# Relays.net
KiCad netlist of a schematic drawn in Altium Designer
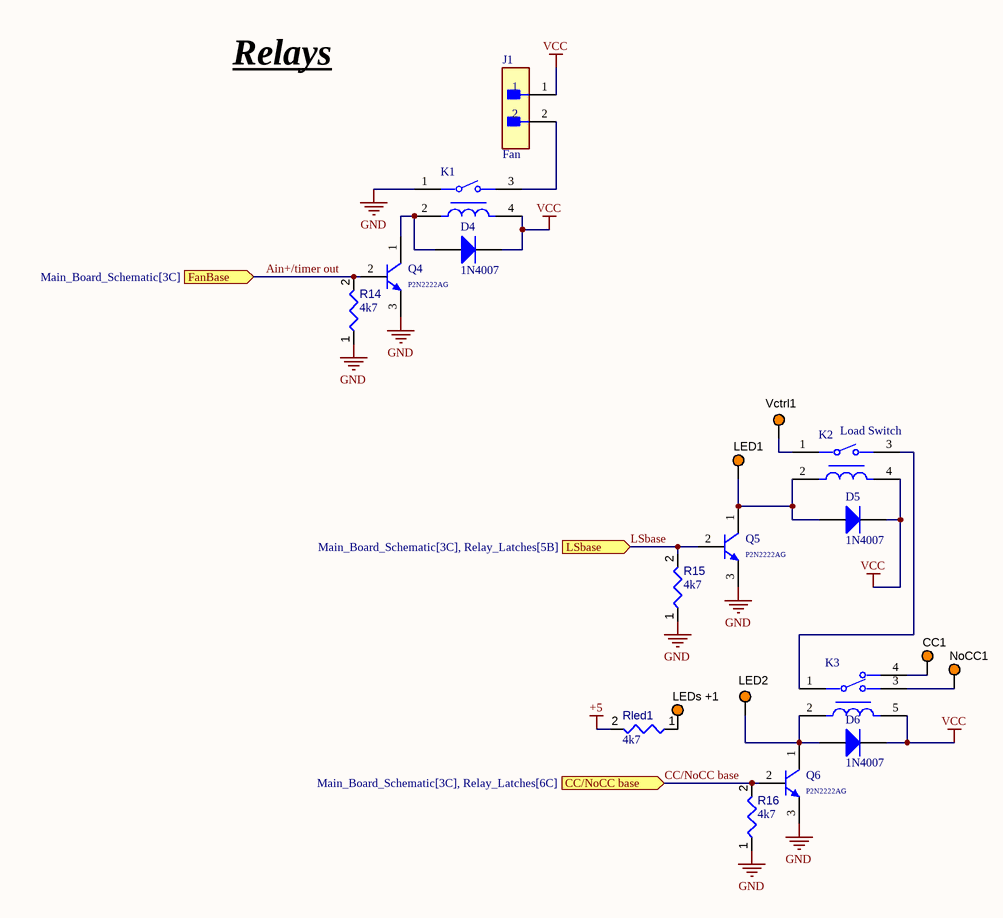
[diagram p0: Relays.SchDoc]

(export (version "E")
  (design (tool "Eeschema 10.0.6"))
  (components
    (comp (ref "CC1")
      (value "5003")
      (footprint "KSTN-5003")
      (description "Test Point, Orange, Height 4.6 mm, Tail Length 3 mm, 1-Pin THD, RoHS")
      (fields (field (name "MANUFACTURER") "Keystone"))
      (libsource (lib "Konstantinos Psarras") (part "TESTPOINT_ORANGE"))
    )
    (comp (ref "D4")
      (value "1N4007")
      (footprint "FAIR-DO-41-2")
      (description "General Purpose Rectifier, 1.1 V, 1.0 A, -55 to 175 degC, 2-Pin DO-41, RoHS, Tape and Reel")
      (fields (field (name "MANUFACTURER") "Fairchild"))
      (libsource (lib "Konstantinos Psarras") (part "KESE-D_K1A2-2"))
    )
    (comp (ref "D5")
      (value "1N4007")
      (footprint "FAIR-DO-41-2")
      (description "General Purpose Rectifier, 1.1 V, 1.0 A, -55 to 175 degC, 2-Pin DO-41, RoHS, Tape and Reel")
      (fields (field (name "MANUFACTURER") "Fairchild"))
      (libsource (lib "Konstantinos Psarras") (part "KESE-D_K1A2-2"))
    )
    (comp (ref "D6")
      (value "1N4007")
      (footprint "FAIR-DO-41-2")
      (description "General Purpose Rectifier, 1.1 V, 1.0 A, -55 to 175 degC, 2-Pin DO-41, RoHS, Tape and Reel")
      (fields (field (name "MANUFACTURER") "Fairchild"))
      (libsource (lib "Konstantinos Psarras") (part "KESE-D_K1A2-2"))
    )
    (comp (ref "J1")
      (value "Fan")
      (footprint "FP-B2B-XH-A_LF_SN-MFG")
      (description "CONN HEADER VERT 2POS 2.5MM")
      (libsource (lib "Altium Content Vault") (part "3bc925449376181038e59eaffc5286c"))
    )
    (comp (ref "K1")
      (value "LKQ1AF-5V-TV-5")
      (footprint "FP-LKQ1AF-5V-TV-5-MFG")
      (description "Quiet Type, High Sensitivity 250MW, Slim Power Relay")
      (libsource (lib "Konstantinos Psarras") (part "efdf740da079d6e8343da2175463948"))
    )
    (comp (ref "K2")
      (value "Load Switch")
      (footprint "FP-LKQ1AF-5V-TV-5-MFG")
      (description "Quiet Type, High Sensitivity 250MW, Slim Power Relay")
      (libsource (lib "Konstantinos Psarras") (part "efdf740da079d6e8343da2175463948"))
    )
    (comp (ref "K3")
      (value "G5LE-14-36 DC12")
      (footprint "FP-G5LE-14-36_DC12-MFG")
      (description "RELAY GEN PURPOSE SPDT 10A 12V")
      (libsource (lib "Altium Content Vault") (part "c03b8d08e5d02e70a6880f365e34168"))
    )
    (comp (ref "LED1")
      (value "5003")
      (footprint "KSTN-5003")
      (description "Test Point, Orange, Height 4.6 mm, Tail Length 3 mm, 1-Pin THD, RoHS")
      (fields (field (name "MANUFACTURER") "Keystone"))
      (libsource (lib "Konstantinos Psarras") (part "TESTPOINT_ORANGE"))
    )
    (comp (ref "LED2")
      (value "5003")
      (footprint "KSTN-5003")
      (description "Test Point, Orange, Height 4.6 mm, Tail Length 3 mm, 1-Pin THD, RoHS")
      (fields (field (name "MANUFACTURER") "Keystone"))
      (libsource (lib "Konstantinos Psarras") (part "TESTPOINT_ORANGE"))
    )
    (comp (ref "LEDs +1")
      (value "5003")
      (footprint "KSTN-5003")
      (description "Test Point, Orange, Height 4.6 mm, Tail Length 3 mm, 1-Pin THD, RoHS")
      (fields (field (name "MANUFACTURER") "Keystone"))
      (libsource (lib "Konstantinos Psarras") (part "TESTPOINT_ORANGE"))
    )
    (comp (ref "NoCC1")
      (value "5003")
      (footprint "KSTN-5003")
      (description "Test Point, Orange, Height 4.6 mm, Tail Length 3 mm, 1-Pin THD, RoHS")
      (fields (field (name "MANUFACTURER") "Keystone"))
      (libsource (lib "Konstantinos Psarras") (part "TESTPOINT_ORANGE"))
    )
    (comp (ref "Q4")
      (value "P2N2222AG")
      (footprint "ONSC-TO-92-3-29-11")
      (description "Amplifier Transistor, NPN Silicon, 3-Pin TO-92, Pb-Free, Bulk Box")
      (fields (field (name "MANUFACTURER") "On Semiconductor"))
      (libsource (lib "Altium Content Vault") (part "ONSC-NPN-C1B2E3-3"))
    )
    (comp (ref "Q5")
      (value "P2N2222AG")
      (footprint "ONSC-TO-92-3-29-11")
      (description "Amplifier Transistor, NPN Silicon, 3-Pin TO-92, Pb-Free, Bulk Box")
      (fields (field (name "MANUFACTURER") "On Semiconductor"))
      (libsource (lib "Altium Content Vault") (part "ONSC-NPN-C1B2E3-3"))
    )
    (comp (ref "Q6")
      (value "P2N2222AG")
      (footprint "ONSC-TO-92-3-29-11")
      (description "Amplifier Transistor, NPN Silicon, 3-Pin TO-92, Pb-Free, Bulk Box")
      (fields (field (name "MANUFACTURER") "On Semiconductor"))
      (libsource (lib "Altium Content Vault") (part "ONSC-NPN-C1B2E3-3"))
    )
    (comp (ref "R14")
      (value "4k7")
      (footprint "RESA60-630X240")
      (description "Axial Resistor, 100 Ohm, +/- 1%, 0.25 W, -55 to 155 degC, 2-Pin THD, RoHS, Bulk")
      (fields (field (name "MANUFACTURER") "Yageo") (field (name "TOLERANCE") "1%"))
      (libsource (lib "Konstantinos Psarras") (part "RES-2"))
    )
    (comp (ref "R15")
      (value "4k7")
      (footprint "RESA60-630X240")
      (description "Axial Resistor, 100 Ohm, +/- 1%, 0.25 W, -55 to 155 degC, 2-Pin THD, RoHS, Bulk")
      (fields (field (name "MANUFACTURER") "Yageo") (field (name "TOLERANCE") "1%"))
      (libsource (lib "Konstantinos Psarras") (part "RES-2"))
    )
    (comp (ref "R16")
      (value "4k7")
      (footprint "RESA60-630X240")
      (description "Axial Resistor, 100 Ohm, +/- 1%, 0.25 W, -55 to 155 degC, 2-Pin THD, RoHS, Bulk")
      (fields (field (name "MANUFACTURER") "Yageo") (field (name "TOLERANCE") "1%"))
      (libsource (lib "Konstantinos Psarras") (part "RES-2"))
    )
    (comp (ref "Rled1")
      (value "4k7")
      (footprint "RESA60-630X240")
      (description "Axial Resistor, 100 Ohm, +/- 1%, 0.25 W, -55 to 155 degC, 2-Pin THD, RoHS, Bulk")
      (fields (field (name "MANUFACTURER") "Yageo") (field (name "TOLERANCE") "1%"))
      (libsource (lib "Konstantinos Psarras") (part "RES-2"))
    )
    (comp (ref "Vctrl1")
      (value "5003")
      (footprint "KSTN-5003")
      (description "Test Point, Orange, Height 4.6 mm, Tail Length 3 mm, 1-Pin THD, RoHS")
      (fields (field (name "MANUFACTURER") "Keystone"))
      (libsource (lib "Konstantinos Psarras") (part "TESTPOINT_ORANGE"))
    )
  )
  (nets
    (net (code "1") (name "+5") (class "Default")
      (node (ref "Rled1") (pin "2") (pinfunction "2_2") (pintype "passive"))
    )
    (net (code "2") (name "/Ain+{slash}timer out") (class "Default")
      (node (ref "Q4") (pin "2") (pinfunction "B_2") (pintype "passive"))
      (node (ref "R14") (pin "2") (pinfunction "2_2") (pintype "passive"))
    )
    (net (code "3") (name "/CC{slash}NoCC base") (class "Default")
      (node (ref "Q6") (pin "2") (pinfunction "B_2") (pintype "passive"))
      (node (ref "R16") (pin "2") (pinfunction "2_2") (pintype "passive"))
    )
    (net (code "4") (name "/LSbase") (class "Default")
      (node (ref "Q5") (pin "2") (pinfunction "B_2") (pintype "passive"))
      (node (ref "R15") (pin "2") (pinfunction "2_2") (pintype "passive"))
    )
    (net (code "5") (name "GND") (class "Default")
      (node (ref "K1") (pin "1") (pinfunction "1_1") (pintype "passive"))
      (node (ref "Q4") (pin "3") (pinfunction "E_3") (pintype "passive"))
      (node (ref "Q5") (pin "3") (pinfunction "E_3") (pintype "passive"))
      (node (ref "Q6") (pin "3") (pinfunction "E_3") (pintype "passive"))
      (node (ref "R14") (pin "1") (pinfunction "1_1") (pintype "passive"))
      (node (ref "R15") (pin "1") (pinfunction "1_1") (pintype "passive"))
      (node (ref "R16") (pin "1") (pinfunction "1_1") (pintype "passive"))
    )
    (net (code "6") (name "Net-(CC1-Pad1)") (class "Default")
      (node (ref "CC1") (pin "1") (pinfunction "1_1") (pintype "passive"))
      (node (ref "K3") (pin "4") (pinfunction "4_4") (pintype "passive"))
    )
    (net (code "7") (name "Net-(D4-A)") (class "Default")
      (node (ref "D4") (pin "2") (pinfunction "A_2") (pintype "passive"))
      (node (ref "K1") (pin "2") (pinfunction "2_2") (pintype "passive"))
      (node (ref "Q4") (pin "1") (pinfunction "C_1") (pintype "passive"))
    )
    (net (code "8") (name "Net-(D5-A)") (class "Default")
      (node (ref "D5") (pin "2") (pinfunction "A_2") (pintype "passive"))
      (node (ref "K2") (pin "2") (pinfunction "2_2") (pintype "passive"))
      (node (ref "LED1") (pin "1") (pinfunction "1_1") (pintype "passive"))
      (node (ref "Q5") (pin "1") (pinfunction "C_1") (pintype "passive"))
    )
    (net (code "9") (name "Net-(D6-A)") (class "Default")
      (node (ref "D6") (pin "2") (pinfunction "A_2") (pintype "passive"))
      (node (ref "K3") (pin "2") (pinfunction "2_2") (pintype "passive"))
      (node (ref "LED2") (pin "1") (pinfunction "1_1") (pintype "passive"))
      (node (ref "Q6") (pin "1") (pinfunction "C_1") (pintype "passive"))
    )
    (net (code "10") (name "Net-(J1-Pad2)") (class "Default")
      (node (ref "J1") (pin "2") (pinfunction "2_2") (pintype "passive"))
      (node (ref "K1") (pin "3") (pinfunction "3_3") (pintype "passive"))
    )
    (net (code "11") (name "Net-(K2-Pad1)") (class "Default")
      (node (ref "K2") (pin "1") (pinfunction "1_1") (pintype "passive"))
      (node (ref "Vctrl1") (pin "1") (pinfunction "1_1") (pintype "passive"))
    )
    (net (code "12") (name "Net-(K2-Pad3)") (class "Default")
      (node (ref "K2") (pin "3") (pinfunction "3_3") (pintype "passive"))
      (node (ref "K3") (pin "1") (pinfunction "1_1") (pintype "passive"))
    )
    (net (code "13") (name "Net-(K3-Pad3)") (class "Default")
      (node (ref "K3") (pin "3") (pinfunction "3_3") (pintype "passive"))
      (node (ref "NoCC1") (pin "1") (pinfunction "1_1") (pintype "passive"))
    )
    (net (code "14") (name "Net-(LEDs +1-Pad1)") (class "Default")
      (node (ref "LEDs +1") (pin "1") (pinfunction "1_1") (pintype "passive"))
      (node (ref "Rled1") (pin "1") (pinfunction "1_1") (pintype "passive"))
    )
    (net (code "15") (name "VCC") (class "Default")
      (node (ref "D4") (pin "1") (pinfunction "K_1") (pintype "passive"))
      (node (ref "D5") (pin "1") (pinfunction "K_1") (pintype "passive"))
      (node (ref "D6") (pin "1") (pinfunction "K_1") (pintype "passive"))
      (node (ref "J1") (pin "1") (pinfunction "1_1") (pintype "passive"))
      (node (ref "K1") (pin "4") (pinfunction "4_4") (pintype "passive"))
      (node (ref "K2") (pin "4") (pinfunction "4_4") (pintype "passive"))
      (node (ref "K3") (pin "5") (pinfunction "5_5") (pintype "passive"))
    )
  )
)
